# ADC_Board_Two_Board_Molex.net
KiCad netlist of a schematic drawn in EAGLE
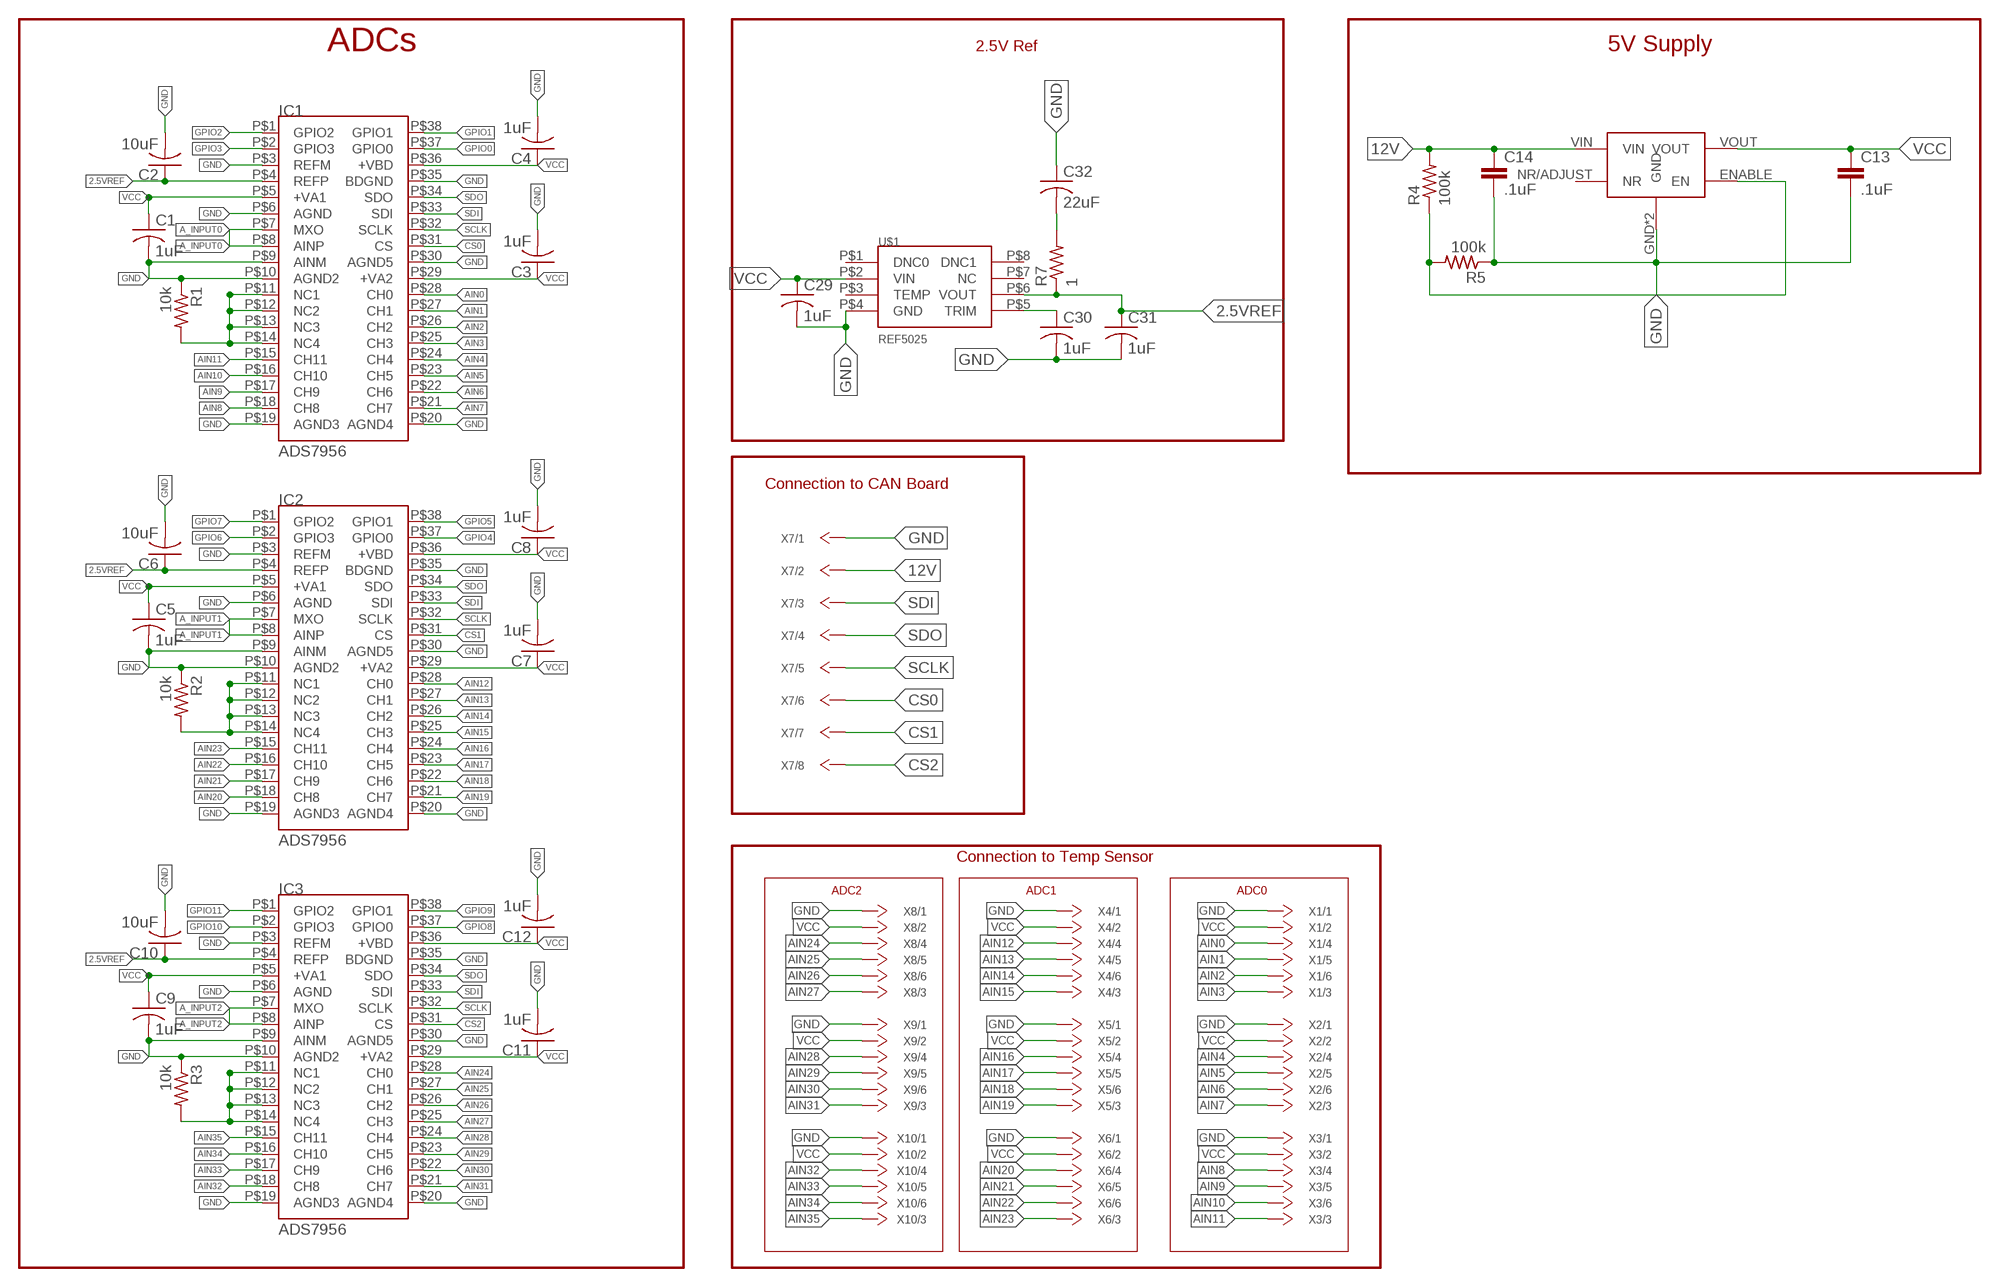
[diagram p0: schematic, sheet 1]

(export (version "E")
  (design (tool "Eeschema 10.0.6"))
  (components
    (comp (ref "C1")
      (value "1uF")
      (footprint "eagle-import:C0603")
      (libsource (lib "eagle-import") (part "C-USC0603"))
    )
    (comp (ref "C2")
      (value "10uF")
      (footprint "eagle-import:C0603")
      (libsource (lib "eagle-import") (part "C-USC0603"))
    )
    (comp (ref "C3")
      (value "1uF")
      (footprint "eagle-import:C0603")
      (libsource (lib "eagle-import") (part "C-USC0603"))
    )
    (comp (ref "C4")
      (value "1uF")
      (footprint "eagle-import:C0603")
      (libsource (lib "eagle-import") (part "C-USC0603"))
    )
    (comp (ref "C5")
      (value "1uF")
      (footprint "eagle-import:C0603")
      (libsource (lib "eagle-import") (part "C-USC0603"))
    )
    (comp (ref "C6")
      (value "10uF")
      (footprint "eagle-import:C0603")
      (libsource (lib "eagle-import") (part "C-USC0603"))
    )
    (comp (ref "C7")
      (value "1uF")
      (footprint "eagle-import:C0603")
      (libsource (lib "eagle-import") (part "C-USC0603"))
    )
    (comp (ref "C8")
      (value "1uF")
      (footprint "eagle-import:C0603")
      (libsource (lib "eagle-import") (part "C-USC0603"))
    )
    (comp (ref "C9")
      (value "1uF")
      (footprint "eagle-import:C0603")
      (libsource (lib "eagle-import") (part "C-USC0603"))
    )
    (comp (ref "C10")
      (value "10uF")
      (footprint "eagle-import:C0603")
      (libsource (lib "eagle-import") (part "C-USC0603"))
    )
    (comp (ref "C11")
      (value "1uF")
      (footprint "eagle-import:C0603")
      (libsource (lib "eagle-import") (part "C-USC0603"))
    )
    (comp (ref "C12")
      (value "1uF")
      (footprint "eagle-import:C0603")
      (libsource (lib "eagle-import") (part "C-USC0603"))
    )
    (comp (ref "C13")
      (value ".1uF")
      (footprint "eagle-import:C0603")
      (libsource (lib "eagle-import") (part "C-EUC0603"))
    )
    (comp (ref "C14")
      (value ".1uF")
      (footprint "eagle-import:C0603")
      (libsource (lib "eagle-import") (part "C-EUC0603"))
    )
    (comp (ref "C29")
      (value "1uF")
      (footprint "eagle-import:C0603")
      (libsource (lib "eagle-import") (part "C-USC0603"))
    )
    (comp (ref "C30")
      (value "1uF")
      (footprint "eagle-import:C0603")
      (libsource (lib "eagle-import") (part "C-USC0603"))
    )
    (comp (ref "C31")
      (value "1uF")
      (footprint "eagle-import:C0603")
      (libsource (lib "eagle-import") (part "C-USC0603"))
    )
    (comp (ref "C32")
      (value "22uF")
      (footprint "eagle-import:C0603")
      (libsource (lib "eagle-import") (part "C-USC0603"))
    )
    (comp (ref "IC1")
      (value "ADS7956")
      (footprint "eagle-import:TSSOP-38")
      (libsource (lib "eagle-import") (part "ADS7956"))
    )
    (comp (ref "IC2")
      (value "ADS7956")
      (footprint "eagle-import:TSSOP-38")
      (libsource (lib "eagle-import") (part "ADS7956"))
    )
    (comp (ref "IC3")
      (value "ADS7956")
      (footprint "eagle-import:TSSOP-38")
      (libsource (lib "eagle-import") (part "ADS7956"))
    )
    (comp (ref "R1")
      (value "10k")
      (footprint "eagle-import:R0603")
      (libsource (lib "eagle-import") (part "resistor_R-US_R0603"))
    )
    (comp (ref "R2")
      (value "10k")
      (footprint "eagle-import:R0603")
      (libsource (lib "eagle-import") (part "resistor_R-US_R0603"))
    )
    (comp (ref "R3")
      (value "10k")
      (footprint "eagle-import:R0603")
      (libsource (lib "eagle-import") (part "resistor_R-US_R0603"))
    )
    (comp (ref "R4")
      (value "100k")
      (footprint "eagle-import:M0805")
      (libsource (lib "eagle-import") (part "rcl_R-US_M0805"))
    )
    (comp (ref "R5")
      (value "100k")
      (footprint "eagle-import:M0805")
      (libsource (lib "eagle-import") (part "rcl_R-US_M0805"))
    )
    (comp (ref "R7")
      (value "1")
      (footprint "eagle-import:M0805")
      (libsource (lib "eagle-import") (part "R-US_M0805"))
    )
    (comp (ref "U$1")
      (value "REF5025")
      (footprint "eagle-import:TSSOP-8(TI)")
      (libsource (lib "eagle-import") (part "REF5025"))
    )
    (comp (ref "U$2")
      (value "REG-104GA-5")
      (footprint "eagle-import:REG104GA-5")
      (libsource (lib "eagle-import") (part "REG-104GA-5"))
    )
    (comp (ref "X1")
      (value "6_PIN_CONNMOLEX_HORI")
      (footprint "eagle-import:6_PIN_MOLEX")
      (libsource (lib "eagle-import") (part "6_PIN_CONNMOLEX_HORI"))
    )
    (comp (ref "X2")
      (value "6_PIN_CONNMOLEX_HORI")
      (footprint "eagle-import:6_PIN_MOLEX")
      (libsource (lib "eagle-import") (part "6_PIN_CONNMOLEX_HORI"))
    )
    (comp (ref "X3")
      (value "6_PIN_CONNMOLEX_HORI")
      (footprint "eagle-import:6_PIN_MOLEX")
      (libsource (lib "eagle-import") (part "6_PIN_CONNMOLEX_HORI"))
    )
    (comp (ref "X4")
      (value "6_PIN_CONNMOLEX_HORI")
      (footprint "eagle-import:6_PIN_MOLEX")
      (libsource (lib "eagle-import") (part "6_PIN_CONNMOLEX_HORI"))
    )
    (comp (ref "X5")
      (value "6_PIN_CONNMOLEX_HORI")
      (footprint "eagle-import:6_PIN_MOLEX")
      (libsource (lib "eagle-import") (part "6_PIN_CONNMOLEX_HORI"))
    )
    (comp (ref "X6")
      (value "6_PIN_CONNMOLEX_HORI")
      (footprint "eagle-import:6_PIN_MOLEX")
      (libsource (lib "eagle-import") (part "6_PIN_CONNMOLEX_HORI"))
    )
    (comp (ref "X7")
      (value "8_PIN_CONN")
      (footprint "eagle-import:8_PIN_MOLEX")
      (libsource (lib "eagle-import") (part "8_PIN_CONN"))
    )
    (comp (ref "X8")
      (value "6_PIN_CONNMOLEX_HORI")
      (footprint "eagle-import:6_PIN_MOLEX")
      (libsource (lib "eagle-import") (part "6_PIN_CONNMOLEX_HORI"))
    )
    (comp (ref "X9")
      (value "6_PIN_CONNMOLEX_HORI")
      (footprint "eagle-import:6_PIN_MOLEX")
      (libsource (lib "eagle-import") (part "6_PIN_CONNMOLEX_HORI"))
    )
    (comp (ref "X10")
      (value "6_PIN_CONNMOLEX_HORI")
      (footprint "eagle-import:6_PIN_MOLEX")
      (libsource (lib "eagle-import") (part "6_PIN_CONNMOLEX_HORI"))
    )
  )
  (nets
    (net (code "1") (name "2.5VREF") (class "Default")
      (node (ref "C10") (pin "1") (pinfunction "1_1") (pintype "passive"))
      (node (ref "C2") (pin "1") (pinfunction "1_1") (pintype "passive"))
      (node (ref "C31") (pin "1") (pinfunction "1_1") (pintype "passive"))
      (node (ref "C6") (pin "1") (pinfunction "1_1") (pintype "passive"))
      (node (ref "IC1") (pin "P$4") (pinfunction "REFP_P$4") (pintype "bidirectional"))
      (node (ref "IC2") (pin "P$4") (pinfunction "REFP_P$4") (pintype "bidirectional"))
      (node (ref "IC3") (pin "P$4") (pinfunction "REFP_P$4") (pintype "bidirectional"))
      (node (ref "R7") (pin "1") (pinfunction "1_1") (pintype "passive"))
      (node (ref "U$1") (pin "P$6") (pinfunction "VOUT_P$6") (pintype "bidirectional"))
    )
    (net (code "2") (name "12V") (class "Default")
      (node (ref "C14") (pin "1") (pinfunction "1_1") (pintype "passive"))
      (node (ref "R4") (pin "2") (pinfunction "2_2") (pintype "passive"))
      (node (ref "U$2") (pin "VIN") (pinfunction "VIN_VIN") (pintype "bidirectional"))
      (node (ref "X7") (pin "P$2") (pinfunction "$/1_P$2") (pintype "bidirectional"))
    )
    (net (code "3") (name "AIN0") (class "Default")
      (node (ref "IC1") (pin "P$28") (pinfunction "CH0_P$28") (pintype "bidirectional"))
      (node (ref "X1") (pin "P$4") (pinfunction "$/1_P$4") (pintype "bidirectional"))
    )
    (net (code "4") (name "AIN1") (class "Default")
      (node (ref "IC1") (pin "P$27") (pinfunction "CH1_P$27") (pintype "bidirectional"))
      (node (ref "X1") (pin "P$5") (pinfunction "$/1_P$5") (pintype "bidirectional"))
    )
    (net (code "5") (name "AIN2") (class "Default")
      (node (ref "IC1") (pin "P$26") (pinfunction "CH2_P$26") (pintype "bidirectional"))
      (node (ref "X1") (pin "P$6") (pinfunction "$/1_P$6") (pintype "bidirectional"))
    )
    (net (code "6") (name "AIN3") (class "Default")
      (node (ref "IC1") (pin "P$25") (pinfunction "CH3_P$25") (pintype "bidirectional"))
      (node (ref "X1") (pin "P$3") (pinfunction "$/1_P$3") (pintype "bidirectional"))
    )
    (net (code "7") (name "AIN4") (class "Default")
      (node (ref "IC1") (pin "P$24") (pinfunction "CH4_P$24") (pintype "bidirectional"))
      (node (ref "X2") (pin "P$4") (pinfunction "$/1_P$4") (pintype "bidirectional"))
    )
    (net (code "8") (name "AIN5") (class "Default")
      (node (ref "IC1") (pin "P$23") (pinfunction "CH5_P$23") (pintype "bidirectional"))
      (node (ref "X2") (pin "P$5") (pinfunction "$/1_P$5") (pintype "bidirectional"))
    )
    (net (code "9") (name "AIN6") (class "Default")
      (node (ref "IC1") (pin "P$22") (pinfunction "CH6_P$22") (pintype "bidirectional"))
      (node (ref "X2") (pin "P$6") (pinfunction "$/1_P$6") (pintype "bidirectional"))
    )
    (net (code "10") (name "AIN7") (class "Default")
      (node (ref "IC1") (pin "P$21") (pinfunction "CH7_P$21") (pintype "bidirectional"))
      (node (ref "X2") (pin "P$3") (pinfunction "$/1_P$3") (pintype "bidirectional"))
    )
    (net (code "11") (name "AIN8") (class "Default")
      (node (ref "IC1") (pin "P$18") (pinfunction "CH8_P$18") (pintype "bidirectional"))
      (node (ref "X3") (pin "P$4") (pinfunction "$/1_P$4") (pintype "bidirectional"))
    )
    (net (code "12") (name "AIN9") (class "Default")
      (node (ref "IC1") (pin "P$17") (pinfunction "CH9_P$17") (pintype "bidirectional"))
      (node (ref "X3") (pin "P$5") (pinfunction "$/1_P$5") (pintype "bidirectional"))
    )
    (net (code "13") (name "AIN10") (class "Default")
      (node (ref "IC1") (pin "P$16") (pinfunction "CH10_P$16") (pintype "bidirectional"))
      (node (ref "X3") (pin "P$6") (pinfunction "$/1_P$6") (pintype "bidirectional"))
    )
    (net (code "14") (name "AIN11") (class "Default")
      (node (ref "IC1") (pin "P$15") (pinfunction "CH11_P$15") (pintype "bidirectional"))
      (node (ref "X3") (pin "P$3") (pinfunction "$/1_P$3") (pintype "bidirectional"))
    )
    (net (code "15") (name "AIN12") (class "Default")
      (node (ref "IC2") (pin "P$28") (pinfunction "CH0_P$28") (pintype "bidirectional"))
      (node (ref "X4") (pin "P$4") (pinfunction "$/1_P$4") (pintype "bidirectional"))
    )
    (net (code "16") (name "AIN13") (class "Default")
      (node (ref "IC2") (pin "P$27") (pinfunction "CH1_P$27") (pintype "bidirectional"))
      (node (ref "X4") (pin "P$5") (pinfunction "$/1_P$5") (pintype "bidirectional"))
    )
    (net (code "17") (name "AIN14") (class "Default")
      (node (ref "IC2") (pin "P$26") (pinfunction "CH2_P$26") (pintype "bidirectional"))
      (node (ref "X4") (pin "P$6") (pinfunction "$/1_P$6") (pintype "bidirectional"))
    )
    (net (code "18") (name "AIN15") (class "Default")
      (node (ref "IC2") (pin "P$25") (pinfunction "CH3_P$25") (pintype "bidirectional"))
      (node (ref "X4") (pin "P$3") (pinfunction "$/1_P$3") (pintype "bidirectional"))
    )
    (net (code "19") (name "AIN16") (class "Default")
      (node (ref "IC2") (pin "P$24") (pinfunction "CH4_P$24") (pintype "bidirectional"))
      (node (ref "X5") (pin "P$4") (pinfunction "$/1_P$4") (pintype "bidirectional"))
    )
    (net (code "20") (name "AIN17") (class "Default")
      (node (ref "IC2") (pin "P$23") (pinfunction "CH5_P$23") (pintype "bidirectional"))
      (node (ref "X5") (pin "P$5") (pinfunction "$/1_P$5") (pintype "bidirectional"))
    )
    (net (code "21") (name "AIN18") (class "Default")
      (node (ref "IC2") (pin "P$22") (pinfunction "CH6_P$22") (pintype "bidirectional"))
      (node (ref "X5") (pin "P$6") (pinfunction "$/1_P$6") (pintype "bidirectional"))
    )
    (net (code "22") (name "AIN19") (class "Default")
      (node (ref "IC2") (pin "P$21") (pinfunction "CH7_P$21") (pintype "bidirectional"))
      (node (ref "X5") (pin "P$3") (pinfunction "$/1_P$3") (pintype "bidirectional"))
    )
    (net (code "23") (name "AIN20") (class "Default")
      (node (ref "IC2") (pin "P$18") (pinfunction "CH8_P$18") (pintype "bidirectional"))
      (node (ref "X6") (pin "P$4") (pinfunction "$/1_P$4") (pintype "bidirectional"))
    )
    (net (code "24") (name "AIN21") (class "Default")
      (node (ref "IC2") (pin "P$17") (pinfunction "CH9_P$17") (pintype "bidirectional"))
      (node (ref "X6") (pin "P$5") (pinfunction "$/1_P$5") (pintype "bidirectional"))
    )
    (net (code "25") (name "AIN22") (class "Default")
      (node (ref "IC2") (pin "P$16") (pinfunction "CH10_P$16") (pintype "bidirectional"))
      (node (ref "X6") (pin "P$6") (pinfunction "$/1_P$6") (pintype "bidirectional"))
    )
    (net (code "26") (name "AIN23") (class "Default")
      (node (ref "IC2") (pin "P$15") (pinfunction "CH11_P$15") (pintype "bidirectional"))
      (node (ref "X6") (pin "P$3") (pinfunction "$/1_P$3") (pintype "bidirectional"))
    )
    (net (code "27") (name "AIN24") (class "Default")
      (node (ref "IC3") (pin "P$28") (pinfunction "CH0_P$28") (pintype "bidirectional"))
      (node (ref "X8") (pin "P$4") (pinfunction "$/1_P$4") (pintype "bidirectional"))
    )
    (net (code "28") (name "AIN25") (class "Default")
      (node (ref "IC3") (pin "P$27") (pinfunction "CH1_P$27") (pintype "bidirectional"))
      (node (ref "X8") (pin "P$5") (pinfunction "$/1_P$5") (pintype "bidirectional"))
    )
    (net (code "29") (name "AIN26") (class "Default")
      (node (ref "IC3") (pin "P$26") (pinfunction "CH2_P$26") (pintype "bidirectional"))
      (node (ref "X8") (pin "P$6") (pinfunction "$/1_P$6") (pintype "bidirectional"))
    )
    (net (code "30") (name "AIN27") (class "Default")
      (node (ref "IC3") (pin "P$25") (pinfunction "CH3_P$25") (pintype "bidirectional"))
      (node (ref "X8") (pin "P$3") (pinfunction "$/1_P$3") (pintype "bidirectional"))
    )
    (net (code "31") (name "AIN28") (class "Default")
      (node (ref "IC3") (pin "P$24") (pinfunction "CH4_P$24") (pintype "bidirectional"))
      (node (ref "X9") (pin "P$4") (pinfunction "$/1_P$4") (pintype "bidirectional"))
    )
    (net (code "32") (name "AIN29") (class "Default")
      (node (ref "IC3") (pin "P$23") (pinfunction "CH5_P$23") (pintype "bidirectional"))
      (node (ref "X9") (pin "P$5") (pinfunction "$/1_P$5") (pintype "bidirectional"))
    )
    (net (code "33") (name "AIN30") (class "Default")
      (node (ref "IC3") (pin "P$22") (pinfunction "CH6_P$22") (pintype "bidirectional"))
      (node (ref "X9") (pin "P$6") (pinfunction "$/1_P$6") (pintype "bidirectional"))
    )
    (net (code "34") (name "AIN31") (class "Default")
      (node (ref "IC3") (pin "P$21") (pinfunction "CH7_P$21") (pintype "bidirectional"))
      (node (ref "X9") (pin "P$3") (pinfunction "$/1_P$3") (pintype "bidirectional"))
    )
    (net (code "35") (name "AIN32") (class "Default")
      (node (ref "IC3") (pin "P$18") (pinfunction "CH8_P$18") (pintype "bidirectional"))
      (node (ref "X10") (pin "P$4") (pinfunction "$/1_P$4") (pintype "bidirectional"))
    )
    (net (code "36") (name "AIN33") (class "Default")
      (node (ref "IC3") (pin "P$17") (pinfunction "CH9_P$17") (pintype "bidirectional"))
      (node (ref "X10") (pin "P$5") (pinfunction "$/1_P$5") (pintype "bidirectional"))
    )
    (net (code "37") (name "AIN34") (class "Default")
      (node (ref "IC3") (pin "P$16") (pinfunction "CH10_P$16") (pintype "bidirectional"))
      (node (ref "X10") (pin "P$6") (pinfunction "$/1_P$6") (pintype "bidirectional"))
    )
    (net (code "38") (name "AIN35") (class "Default")
      (node (ref "IC3") (pin "P$15") (pinfunction "CH11_P$15") (pintype "bidirectional"))
      (node (ref "X10") (pin "P$3") (pinfunction "$/1_P$3") (pintype "bidirectional"))
    )
    (net (code "39") (name "A_INPUT0") (class "Default")
      (node (ref "IC1") (pin "P$7") (pinfunction "MXO_P$7") (pintype "bidirectional"))
      (node (ref "IC1") (pin "P$8") (pinfunction "AINP_P$8") (pintype "bidirectional"))
    )
    (net (code "40") (name "A_INPUT1") (class "Default")
      (node (ref "IC2") (pin "P$7") (pinfunction "MXO_P$7") (pintype "bidirectional"))
      (node (ref "IC2") (pin "P$8") (pinfunction "AINP_P$8") (pintype "bidirectional"))
    )
    (net (code "41") (name "A_INPUT2") (class "Default")
      (node (ref "IC3") (pin "P$7") (pinfunction "MXO_P$7") (pintype "bidirectional"))
      (node (ref "IC3") (pin "P$8") (pinfunction "AINP_P$8") (pintype "bidirectional"))
    )
    (net (code "42") (name "CS0") (class "Default")
      (node (ref "IC1") (pin "P$31") (pinfunction "CS_P$31") (pintype "bidirectional"))
      (node (ref "X7") (pin "P$6") (pinfunction "$/1_P$6") (pintype "bidirectional"))
    )
    (net (code "43") (name "CS1") (class "Default")
      (node (ref "IC2") (pin "P$31") (pinfunction "CS_P$31") (pintype "bidirectional"))
      (node (ref "X7") (pin "P$7") (pinfunction "$/1_P$7") (pintype "bidirectional"))
    )
    (net (code "44") (name "CS2") (class "Default")
      (node (ref "IC3") (pin "P$31") (pinfunction "CS_P$31") (pintype "bidirectional"))
      (node (ref "X7") (pin "P$8") (pinfunction "$/1_P$8") (pintype "bidirectional"))
    )
    (net (code "45") (name "GND") (class "Default")
      (node (ref "C1") (pin "2") (pinfunction "2_2") (pintype "passive"))
      (node (ref "C10") (pin "2") (pinfunction "2_2") (pintype "passive"))
      (node (ref "C11") (pin "2") (pinfunction "2_2") (pintype "passive"))
      (node (ref "C12") (pin "2") (pinfunction "2_2") (pintype "passive"))
      (node (ref "C13") (pin "2") (pinfunction "2_2") (pintype "passive"))
      (node (ref "C14") (pin "2") (pinfunction "2_2") (pintype "passive"))
      (node (ref "C2") (pin "2") (pinfunction "2_2") (pintype "passive"))
      (node (ref "C29") (pin "2") (pinfunction "2_2") (pintype "passive"))
      (node (ref "C3") (pin "2") (pinfunction "2_2") (pintype "passive"))
      (node (ref "C30") (pin "2") (pinfunction "2_2") (pintype "passive"))
      (node (ref "C31") (pin "2") (pinfunction "2_2") (pintype "passive"))
      (node (ref "C32") (pin "1") (pinfunction "1_1") (pintype "passive"))
      (node (ref "C4") (pin "2") (pinfunction "2_2") (pintype "passive"))
      (node (ref "C5") (pin "2") (pinfunction "2_2") (pintype "passive"))
      (node (ref "C6") (pin "2") (pinfunction "2_2") (pintype "passive"))
      (node (ref "C7") (pin "2") (pinfunction "2_2") (pintype "passive"))
      (node (ref "C8") (pin "2") (pinfunction "2_2") (pintype "passive"))
      (node (ref "C9") (pin "2") (pinfunction "2_2") (pintype "passive"))
      (node (ref "IC1") (pin "P$10") (pinfunction "AGND2_P$10") (pintype "bidirectional"))
      (node (ref "IC1") (pin "P$19") (pinfunction "AGND3_P$19") (pintype "bidirectional"))
      (node (ref "IC1") (pin "P$20") (pinfunction "AGND4_P$20") (pintype "bidirectional"))
      (node (ref "IC1") (pin "P$3") (pinfunction "REFM_P$3") (pintype "bidirectional"))
      (node (ref "IC1") (pin "P$30") (pinfunction "AGND5_P$30") (pintype "bidirectional"))
      (node (ref "IC1") (pin "P$35") (pinfunction "BDGND_P$35") (pintype "bidirectional"))
      (node (ref "IC1") (pin "P$6") (pinfunction "AGND_P$6") (pintype "bidirectional"))
      (node (ref "IC1") (pin "P$9") (pinfunction "AINM_P$9") (pintype "bidirectional"))
      (node (ref "IC2") (pin "P$10") (pinfunction "AGND2_P$10") (pintype "bidirectional"))
      (node (ref "IC2") (pin "P$19") (pinfunction "AGND3_P$19") (pintype "bidirectional"))
      (node (ref "IC2") (pin "P$20") (pinfunction "AGND4_P$20") (pintype "bidirectional"))
      (node (ref "IC2") (pin "P$3") (pinfunction "REFM_P$3") (pintype "bidirectional"))
      (node (ref "IC2") (pin "P$30") (pinfunction "AGND5_P$30") (pintype "bidirectional"))
      (node (ref "IC2") (pin "P$35") (pinfunction "BDGND_P$35") (pintype "bidirectional"))
      (node (ref "IC2") (pin "P$6") (pinfunction "AGND_P$6") (pintype "bidirectional"))
      (node (ref "IC2") (pin "P$9") (pinfunction "AINM_P$9") (pintype "bidirectional"))
      (node (ref "IC3") (pin "P$10") (pinfunction "AGND2_P$10") (pintype "bidirectional"))
      (node (ref "IC3") (pin "P$19") (pinfunction "AGND3_P$19") (pintype "bidirectional"))
      (node (ref "IC3") (pin "P$20") (pinfunction "AGND4_P$20") (pintype "bidirectional"))
      (node (ref "IC3") (pin "P$3") (pinfunction "REFM_P$3") (pintype "bidirectional"))
      (node (ref "IC3") (pin "P$30") (pinfunction "AGND5_P$30") (pintype "bidirectional"))
      (node (ref "IC3") (pin "P$35") (pinfunction "BDGND_P$35") (pintype "bidirectional"))
      (node (ref "IC3") (pin "P$6") (pinfunction "AGND_P$6") (pintype "bidirectional"))
      (node (ref "IC3") (pin "P$9") (pinfunction "AINM_P$9") (pintype "bidirectional"))
      (node (ref "R1") (pin "1") (pinfunction "1_1") (pintype "passive"))
      (node (ref "R2") (pin "1") (pinfunction "1_1") (pintype "passive"))
      (node (ref "R3") (pin "1") (pinfunction "1_1") (pintype "passive"))
      (node (ref "R5") (pin "1") (pinfunction "1_1") (pintype "passive"))
      (node (ref "U$1") (pin "P$4") (pinfunction "GND_P$4") (pintype "bidirectional"))
      (node (ref "U$2") (pin "GND") (pinfunction "GND_GND") (pintype "bidirectional"))
      (node (ref "U$2") (pin "HEATGND") (pinfunction "GND_HEATGND") (pintype "bidirectional"))
      (node (ref "X1") (pin "P$1") (pinfunction "$/1_P$1") (pintype "bidirectional"))
      (node (ref "X10") (pin "P$1") (pinfunction "$/1_P$1") (pintype "bidirectional"))
      (node (ref "X2") (pin "P$1") (pinfunction "$/1_P$1") (pintype "bidirectional"))
      (node (ref "X3") (pin "P$1") (pinfunction "$/1_P$1") (pintype "bidirectional"))
      (node (ref "X4") (pin "P$1") (pinfunction "$/1_P$1") (pintype "bidirectional"))
      (node (ref "X5") (pin "P$1") (pinfunction "$/1_P$1") (pintype "bidirectional"))
      (node (ref "X6") (pin "P$1") (pinfunction "$/1_P$1") (pintype "bidirectional"))
      (node (ref "X7") (pin "P$1") (pinfunction "$/1_P$1") (pintype "bidirectional"))
      (node (ref "X8") (pin "P$1") (pinfunction "$/1_P$1") (pintype "bidirectional"))
      (node (ref "X9") (pin "P$1") (pinfunction "$/1_P$1") (pintype "bidirectional"))
    )
    (net (code "46") (name "GPIO0") (class "Default")
      (node (ref "IC1") (pin "P$37") (pinfunction "GPIO0_P$37") (pintype "bidirectional"))
    )
    (net (code "47") (name "GPIO1") (class "Default")
      (node (ref "IC1") (pin "P$38") (pinfunction "GPIO1_P$38") (pintype "bidirectional"))
    )
    (net (code "48") (name "GPIO2") (class "Default")
      (node (ref "IC1") (pin "P$1") (pinfunction "GPIO2_P$1") (pintype "bidirectional"))
    )
    (net (code "49") (name "GPIO3") (class "Default")
      (node (ref "IC1") (pin "P$2") (pinfunction "GPIO3_P$2") (pintype "bidirectional"))
    )
    (net (code "50") (name "GPIO4") (class "Default")
      (node (ref "IC2") (pin "P$37") (pinfunction "GPIO0_P$37") (pintype "bidirectional"))
    )
    (net (code "51") (name "GPIO5") (class "Default")
      (node (ref "IC2") (pin "P$38") (pinfunction "GPIO1_P$38") (pintype "bidirectional"))
    )
    (net (code "52") (name "GPIO6") (class "Default")
      (node (ref "IC2") (pin "P$2") (pinfunction "GPIO3_P$2") (pintype "bidirectional"))
    )
    (net (code "53") (name "GPIO7") (class "Default")
      (node (ref "IC2") (pin "P$1") (pinfunction "GPIO2_P$1") (pintype "bidirectional"))
    )
    (net (code "54") (name "GPIO8") (class "Default")
      (node (ref "IC3") (pin "P$37") (pinfunction "GPIO0_P$37") (pintype "bidirectional"))
    )
    (net (code "55") (name "GPIO9") (class "Default")
      (node (ref "IC3") (pin "P$38") (pinfunction "GPIO1_P$38") (pintype "bidirectional"))
    )
    (net (code "56") (name "GPIO10") (class "Default")
      (node (ref "IC3") (pin "P$2") (pinfunction "GPIO3_P$2") (pintype "bidirectional"))
    )
    (net (code "57") (name "GPIO11") (class "Default")
      (node (ref "IC3") (pin "P$1") (pinfunction "GPIO2_P$1") (pintype "bidirectional"))
    )
    (net (code "58") (name "Net-(C32-Pad2)") (class "Default")
      (node (ref "C32") (pin "2") (pinfunction "2_2") (pintype "passive"))
      (node (ref "R7") (pin "2") (pinfunction "2_2") (pintype "passive"))
    )
    (net (code "59") (name "Net-(IC1-NC1)") (class "Default")
      (node (ref "IC1") (pin "P$11") (pinfunction "NC1_P$11") (pintype "bidirectional"))
      (node (ref "IC1") (pin "P$12") (pinfunction "NC2_P$12") (pintype "bidirectional"))
      (node (ref "IC1") (pin "P$13") (pinfunction "NC3_P$13") (pintype "bidirectional"))
      (node (ref "IC1") (pin "P$14") (pinfunction "NC4_P$14") (pintype "bidirectional"))
      (node (ref "R1") (pin "2") (pinfunction "2_2") (pintype "passive"))
    )
    (net (code "60") (name "Net-(IC2-NC1)") (class "Default")
      (node (ref "IC2") (pin "P$11") (pinfunction "NC1_P$11") (pintype "bidirectional"))
      (node (ref "IC2") (pin "P$12") (pinfunction "NC2_P$12") (pintype "bidirectional"))
      (node (ref "IC2") (pin "P$13") (pinfunction "NC3_P$13") (pintype "bidirectional"))
      (node (ref "IC2") (pin "P$14") (pinfunction "NC4_P$14") (pintype "bidirectional"))
      (node (ref "R2") (pin "2") (pinfunction "2_2") (pintype "passive"))
    )
    (net (code "61") (name "Net-(IC3-NC1)") (class "Default")
      (node (ref "IC3") (pin "P$11") (pinfunction "NC1_P$11") (pintype "bidirectional"))
      (node (ref "IC3") (pin "P$12") (pinfunction "NC2_P$12") (pintype "bidirectional"))
      (node (ref "IC3") (pin "P$13") (pinfunction "NC3_P$13") (pintype "bidirectional"))
      (node (ref "IC3") (pin "P$14") (pinfunction "NC4_P$14") (pintype "bidirectional"))
      (node (ref "R3") (pin "2") (pinfunction "2_2") (pintype "passive"))
    )
    (net (code "62") (name "Net-(U$1-TRIM)") (class "Default")
      (node (ref "C30") (pin "1") (pinfunction "1_1") (pintype "passive"))
      (node (ref "U$1") (pin "P$5") (pinfunction "TRIM_P$5") (pintype "bidirectional"))
    )
    (net (code "63") (name "Net-(U$2-EN)") (class "Default")
      (node (ref "R4") (pin "1") (pinfunction "1_1") (pintype "passive"))
      (node (ref "R5") (pin "2") (pinfunction "2_2") (pintype "passive"))
      (node (ref "U$2") (pin "ENABLE") (pinfunction "EN_ENABLE") (pintype "bidirectional"))
    )
    (net (code "64") (name "SCLK") (class "Default")
      (node (ref "IC1") (pin "P$32") (pinfunction "SCLK_P$32") (pintype "bidirectional"))
      (node (ref "IC2") (pin "P$32") (pinfunction "SCLK_P$32") (pintype "bidirectional"))
      (node (ref "IC3") (pin "P$32") (pinfunction "SCLK_P$32") (pintype "bidirectional"))
      (node (ref "X7") (pin "P$5") (pinfunction "$/1_P$5") (pintype "bidirectional"))
    )
    (net (code "65") (name "SDI") (class "Default")
      (node (ref "IC1") (pin "P$33") (pinfunction "SDI_P$33") (pintype "bidirectional"))
      (node (ref "IC2") (pin "P$33") (pinfunction "SDI_P$33") (pintype "bidirectional"))
      (node (ref "IC3") (pin "P$33") (pinfunction "SDI_P$33") (pintype "bidirectional"))
      (node (ref "X7") (pin "P$3") (pinfunction "$/1_P$3") (pintype "bidirectional"))
    )
    (net (code "66") (name "SDO") (class "Default")
      (node (ref "IC1") (pin "P$34") (pinfunction "SDO_P$34") (pintype "bidirectional"))
      (node (ref "IC2") (pin "P$34") (pinfunction "SDO_P$34") (pintype "bidirectional"))
      (node (ref "IC3") (pin "P$34") (pinfunction "SDO_P$34") (pintype "bidirectional"))
      (node (ref "X7") (pin "P$4") (pinfunction "$/1_P$4") (pintype "bidirectional"))
    )
    (net (code "67") (name "VCC") (class "Default")
      (node (ref "C1") (pin "1") (pinfunction "1_1") (pintype "passive"))
      (node (ref "C11") (pin "1") (pinfunction "1_1") (pintype "passive"))
      (node (ref "C12") (pin "1") (pinfunction "1_1") (pintype "passive"))
      (node (ref "C13") (pin "1") (pinfunction "1_1") (pintype "passive"))
      (node (ref "C29") (pin "1") (pinfunction "1_1") (pintype "passive"))
      (node (ref "C3") (pin "1") (pinfunction "1_1") (pintype "passive"))
      (node (ref "C4") (pin "1") (pinfunction "1_1") (pintype "passive"))
      (node (ref "C5") (pin "1") (pinfunction "1_1") (pintype "passive"))
      (node (ref "C7") (pin "1") (pinfunction "1_1") (pintype "passive"))
      (node (ref "C8") (pin "1") (pinfunction "1_1") (pintype "passive"))
      (node (ref "C9") (pin "1") (pinfunction "1_1") (pintype "passive"))
      (node (ref "IC1") (pin "P$29") (pinfunction "+VA2_P$29") (pintype "bidirectional"))
      (node (ref "IC1") (pin "P$36") (pinfunction "+VBD_P$36") (pintype "bidirectional"))
      (node (ref "IC1") (pin "P$5") (pinfunction "+VA1_P$5") (pintype "bidirectional"))
      (node (ref "IC2") (pin "P$29") (pinfunction "+VA2_P$29") (pintype "bidirectional"))
      (node (ref "IC2") (pin "P$36") (pinfunction "+VBD_P$36") (pintype "bidirectional"))
      (node (ref "IC2") (pin "P$5") (pinfunction "+VA1_P$5") (pintype "bidirectional"))
      (node (ref "IC3") (pin "P$29") (pinfunction "+VA2_P$29") (pintype "bidirectional"))
      (node (ref "IC3") (pin "P$36") (pinfunction "+VBD_P$36") (pintype "bidirectional"))
      (node (ref "IC3") (pin "P$5") (pinfunction "+VA1_P$5") (pintype "bidirectional"))
      (node (ref "U$1") (pin "P$2") (pinfunction "VIN_P$2") (pintype "bidirectional"))
      (node (ref "U$2") (pin "VOUT") (pinfunction "VOUT_VOUT") (pintype "bidirectional"))
      (node (ref "X1") (pin "P$2") (pinfunction "$/1_P$2") (pintype "bidirectional"))
      (node (ref "X10") (pin "P$2") (pinfunction "$/1_P$2") (pintype "bidirectional"))
      (node (ref "X2") (pin "P$2") (pinfunction "$/1_P$2") (pintype "bidirectional"))
      (node (ref "X3") (pin "P$2") (pinfunction "$/1_P$2") (pintype "bidirectional"))
      (node (ref "X4") (pin "P$2") (pinfunction "$/1_P$2") (pintype "bidirectional"))
      (node (ref "X5") (pin "P$2") (pinfunction "$/1_P$2") (pintype "bidirectional"))
      (node (ref "X6") (pin "P$2") (pinfunction "$/1_P$2") (pintype "bidirectional"))
      (node (ref "X8") (pin "P$2") (pinfunction "$/1_P$2") (pintype "bidirectional"))
      (node (ref "X9") (pin "P$2") (pinfunction "$/1_P$2") (pintype "bidirectional"))
    )
    (net (code "68") (name "unconnected-(U$1-DNC0-PadP$1)") (class "Default")
      (node (ref "U$1") (pin "P$1") (pinfunction "DNC0_P$1") (pintype "bidirectional"))
    )
    (net (code "69") (name "unconnected-(U$1-DNC1-PadP$8)") (class "Default")
      (node (ref "U$1") (pin "P$8") (pinfunction "DNC1_P$8") (pintype "bidirectional"))
    )
    (net (code "70") (name "unconnected-(U$1-NC-PadP$7)") (class "Default")
      (node (ref "U$1") (pin "P$7") (pinfunction "NC_P$7") (pintype "bidirectional"))
    )
    (net (code "71") (name "unconnected-(U$1-TEMP-PadP$3)") (class "Default")
      (node (ref "U$1") (pin "P$3") (pinfunction "TEMP_P$3") (pintype "bidirectional"))
    )
    (net (code "72") (name "unconnected-(U$2-NR-PadNR{slash}ADJUST)") (class "Default")
      (node (ref "U$2") (pin "NR/ADJUST") (pinfunction "NR_NR/ADJUST") (pintype "bidirectional"))
    )
  )
)
